# Escon.net
KiCad netlist of a schematic drawn in EAGLE
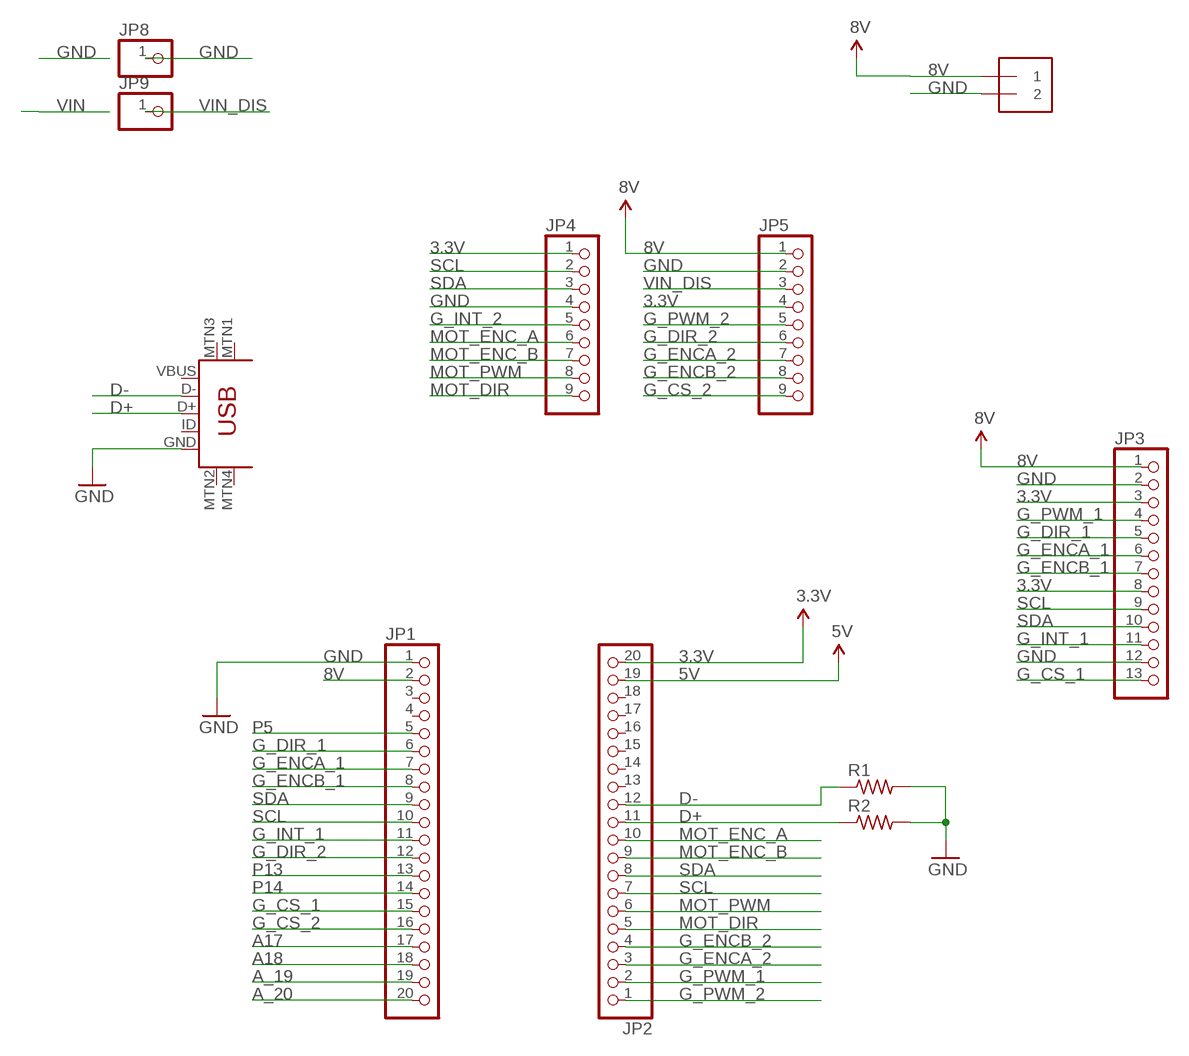
[diagram p0: schematic, sheet 1]

(export (version "E")
  (design (tool "Eeschema 10.0.6"))
  (components
    (comp (ref "J1")
      (value "1X2-3.5MM")
      (footprint "eagle-import:1X2-3.5MM")
      (libsource (lib "eagle-import") (part "1X2-3.5MM"))
    )
    (comp (ref "JP1")
      (value "PINHD-1X20")
      (footprint "eagle-import:1X20")
      (libsource (lib "eagle-import") (part "PINHD-1X20"))
    )
    (comp (ref "JP2")
      (value "PINHD-1X20")
      (footprint "eagle-import:1X20")
      (libsource (lib "eagle-import") (part "PINHD-1X20"))
    )
    (comp (ref "JP3")
      (value "PINHD-1X13")
      (footprint "eagle-import:1X13")
      (libsource (lib "eagle-import") (part "PINHD-1X13"))
    )
    (comp (ref "JP4")
      (value "PINHD-1X9")
      (footprint "eagle-import:1X09-BIG")
      (libsource (lib "eagle-import") (part "PINHD-1X9"))
    )
    (comp (ref "JP5")
      (value "PINHD-1X9")
      (footprint "eagle-import:1X09-BIG")
      (libsource (lib "eagle-import") (part "PINHD-1X9"))
    )
    (comp (ref "JP8")
      (value "PINHD-1X1")
      (footprint "eagle-import:1X01")
      (libsource (lib "eagle-import") (part "PINHD-1X1"))
    )
    (comp (ref "JP9")
      (value "PINHD-1X1")
      (footprint "eagle-import:1X01")
      (libsource (lib "eagle-import") (part "PINHD-1X1"))
    )
    (comp (ref "R1")
      (value "RES-US1206")
      (footprint "eagle-import:R1206")
      (libsource (lib "eagle-import") (part "RES-US1206"))
    )
    (comp (ref "R2")
      (value "RES-US1206")
      (footprint "eagle-import:R1206")
      (libsource (lib "eagle-import") (part "RES-US1206"))
    )
    (comp (ref "U$1")
      (value "USB-MINIB-5PIN")
      (footprint "eagle-import:USB-MINIB")
      (libsource (lib "eagle-import") (part "USB-MINIB-5PIN"))
    )
  )
  (nets
    (net (code "1") (name "/A17") (class "Default")
      (node (ref "JP1") (pin "17") (pinfunction "17_17") (pintype "passive"))
    )
    (net (code "2") (name "/A18") (class "Default")
      (node (ref "JP1") (pin "18") (pinfunction "18_18") (pintype "passive"))
    )
    (net (code "3") (name "/A_19") (class "Default")
      (node (ref "JP1") (pin "19") (pinfunction "19_19") (pintype "passive"))
    )
    (net (code "4") (name "/A_20") (class "Default")
      (node (ref "JP1") (pin "20") (pinfunction "20_20") (pintype "passive"))
    )
    (net (code "5") (name "/D+") (class "Default")
      (node (ref "JP2") (pin "11") (pinfunction "11_11") (pintype "passive"))
      (node (ref "R2") (pin "1") (pinfunction "1_1") (pintype "passive"))
      (node (ref "U$1") (pin "D+") (pinfunction "D+_D+") (pintype "bidirectional"))
    )
    (net (code "6") (name "/D-") (class "Default")
      (node (ref "JP2") (pin "12") (pinfunction "12_12") (pintype "passive"))
      (node (ref "R1") (pin "1") (pinfunction "1_1") (pintype "passive"))
      (node (ref "U$1") (pin "D-") (pinfunction "D-_D-") (pintype "bidirectional"))
    )
    (net (code "7") (name "/G_CS_1") (class "Default")
      (node (ref "JP1") (pin "15") (pinfunction "15_15") (pintype "passive"))
      (node (ref "JP3") (pin "13") (pinfunction "13_13") (pintype "passive"))
    )
    (net (code "8") (name "/G_CS_2") (class "Default")
      (node (ref "JP1") (pin "16") (pinfunction "16_16") (pintype "passive"))
      (node (ref "JP5") (pin "9") (pinfunction "9_9") (pintype "passive"))
    )
    (net (code "9") (name "/G_DIR_1") (class "Default")
      (node (ref "JP1") (pin "6") (pinfunction "6_6") (pintype "passive"))
      (node (ref "JP3") (pin "5") (pinfunction "5_5") (pintype "passive"))
    )
    (net (code "10") (name "/G_DIR_2") (class "Default")
      (node (ref "JP1") (pin "12") (pinfunction "12_12") (pintype "passive"))
      (node (ref "JP5") (pin "6") (pinfunction "6_6") (pintype "passive"))
    )
    (net (code "11") (name "/G_ENCA_1") (class "Default")
      (node (ref "JP1") (pin "7") (pinfunction "7_7") (pintype "passive"))
      (node (ref "JP3") (pin "6") (pinfunction "6_6") (pintype "passive"))
    )
    (net (code "12") (name "/G_ENCA_2") (class "Default")
      (node (ref "JP2") (pin "3") (pinfunction "3_3") (pintype "passive"))
      (node (ref "JP5") (pin "7") (pinfunction "7_7") (pintype "passive"))
    )
    (net (code "13") (name "/G_ENCB_1") (class "Default")
      (node (ref "JP1") (pin "8") (pinfunction "8_8") (pintype "passive"))
      (node (ref "JP3") (pin "7") (pinfunction "7_7") (pintype "passive"))
    )
    (net (code "14") (name "/G_ENCB_2") (class "Default")
      (node (ref "JP2") (pin "4") (pinfunction "4_4") (pintype "passive"))
      (node (ref "JP5") (pin "8") (pinfunction "8_8") (pintype "passive"))
    )
    (net (code "15") (name "/G_INT_1") (class "Default")
      (node (ref "JP1") (pin "11") (pinfunction "11_11") (pintype "passive"))
      (node (ref "JP3") (pin "11") (pinfunction "11_11") (pintype "passive"))
    )
    (net (code "16") (name "/G_INT_2") (class "Default")
      (node (ref "JP4") (pin "5") (pinfunction "5_5") (pintype "passive"))
    )
    (net (code "17") (name "/G_PWM_1") (class "Default")
      (node (ref "JP2") (pin "2") (pinfunction "2_2") (pintype "passive"))
      (node (ref "JP3") (pin "4") (pinfunction "4_4") (pintype "passive"))
    )
    (net (code "18") (name "/G_PWM_2") (class "Default")
      (node (ref "JP2") (pin "1") (pinfunction "1_1") (pintype "passive"))
      (node (ref "JP5") (pin "5") (pinfunction "5_5") (pintype "passive"))
    )
    (net (code "19") (name "/MOT_DIR") (class "Default")
      (node (ref "JP2") (pin "5") (pinfunction "5_5") (pintype "passive"))
      (node (ref "JP4") (pin "9") (pinfunction "9_9") (pintype "passive"))
    )
    (net (code "20") (name "/MOT_ENC_A") (class "Default")
      (node (ref "JP2") (pin "10") (pinfunction "10_10") (pintype "passive"))
      (node (ref "JP4") (pin "6") (pinfunction "6_6") (pintype "passive"))
    )
    (net (code "21") (name "/MOT_ENC_B") (class "Default")
      (node (ref "JP2") (pin "9") (pinfunction "9_9") (pintype "passive"))
      (node (ref "JP4") (pin "7") (pinfunction "7_7") (pintype "passive"))
    )
    (net (code "22") (name "/MOT_PWM") (class "Default")
      (node (ref "JP2") (pin "6") (pinfunction "6_6") (pintype "passive"))
      (node (ref "JP4") (pin "8") (pinfunction "8_8") (pintype "passive"))
    )
    (net (code "23") (name "/P5") (class "Default")
      (node (ref "JP1") (pin "5") (pinfunction "5_5") (pintype "passive"))
    )
    (net (code "24") (name "/P13") (class "Default")
      (node (ref "JP1") (pin "13") (pinfunction "13_13") (pintype "passive"))
    )
    (net (code "25") (name "/P14") (class "Default")
      (node (ref "JP1") (pin "14") (pinfunction "14_14") (pintype "passive"))
    )
    (net (code "26") (name "/SCL") (class "Default")
      (node (ref "JP1") (pin "10") (pinfunction "10_10") (pintype "passive"))
      (node (ref "JP2") (pin "7") (pinfunction "7_7") (pintype "passive"))
      (node (ref "JP3") (pin "9") (pinfunction "9_9") (pintype "passive"))
      (node (ref "JP4") (pin "2") (pinfunction "2_2") (pintype "passive"))
    )
    (net (code "27") (name "/SDA") (class "Default")
      (node (ref "JP1") (pin "9") (pinfunction "9_9") (pintype "passive"))
      (node (ref "JP2") (pin "8") (pinfunction "8_8") (pintype "passive"))
      (node (ref "JP3") (pin "10") (pinfunction "10_10") (pintype "passive"))
      (node (ref "JP4") (pin "3") (pinfunction "3_3") (pintype "passive"))
    )
    (net (code "29") (name "/VIN_DIS") (class "Default")
      (node (ref "JP5") (pin "3") (pinfunction "3_3") (pintype "passive"))
      (node (ref "JP9") (pin "1") (pinfunction "1_1") (pintype "passive"))
    )
    (net (code "30") (name "3.3V") (class "Default")
      (node (ref "JP2") (pin "20") (pinfunction "20_20") (pintype "passive"))
      (node (ref "JP3") (pin "3") (pinfunction "3_3") (pintype "passive"))
      (node (ref "JP3") (pin "8") (pinfunction "8_8") (pintype "passive"))
      (node (ref "JP4") (pin "1") (pinfunction "1_1") (pintype "passive"))
      (node (ref "JP5") (pin "4") (pinfunction "4_4") (pintype "passive"))
    )
    (net (code "31") (name "5V") (class "Default")
      (node (ref "JP2") (pin "19") (pinfunction "19_19") (pintype "passive"))
    )
    (net (code "32") (name "8V") (class "Default")
      (node (ref "J1") (pin "1") (pinfunction "1_1") (pintype "passive"))
      (node (ref "JP1") (pin "2") (pinfunction "2_2") (pintype "passive"))
      (node (ref "JP3") (pin "1") (pinfunction "1_1") (pintype "passive"))
      (node (ref "JP5") (pin "1") (pinfunction "1_1") (pintype "passive"))
    )
    (net (code "33") (name "GND") (class "Default")
      (node (ref "J1") (pin "2") (pinfunction "2_2") (pintype "passive"))
      (node (ref "JP1") (pin "1") (pinfunction "1_1") (pintype "passive"))
      (node (ref "JP3") (pin "12") (pinfunction "12_12") (pintype "passive"))
      (node (ref "JP3") (pin "2") (pinfunction "2_2") (pintype "passive"))
      (node (ref "JP4") (pin "4") (pinfunction "4_4") (pintype "passive"))
      (node (ref "JP5") (pin "2") (pinfunction "2_2") (pintype "passive"))
      (node (ref "JP8") (pin "1") (pinfunction "1_1") (pintype "passive"))
      (node (ref "R1") (pin "2") (pinfunction "2_2") (pintype "passive"))
      (node (ref "R2") (pin "2") (pinfunction "2_2") (pintype "passive"))
      (node (ref "U$1") (pin "GND") (pinfunction "GND_GND") (pintype "bidirectional"))
    )
    (net (code "34") (name "unconnected-(JP1-Pad3)") (class "Default")
      (node (ref "JP1") (pin "3") (pinfunction "3_3") (pintype "passive"))
    )
    (net (code "35") (name "unconnected-(JP1-Pad4)") (class "Default")
      (node (ref "JP1") (pin "4") (pinfunction "4_4") (pintype "passive"))
    )
    (net (code "36") (name "unconnected-(JP2-Pad13)") (class "Default")
      (node (ref "JP2") (pin "13") (pinfunction "13_13") (pintype "passive"))
    )
    (net (code "37") (name "unconnected-(JP2-Pad14)") (class "Default")
      (node (ref "JP2") (pin "14") (pinfunction "14_14") (pintype "passive"))
    )
    (net (code "38") (name "unconnected-(JP2-Pad15)") (class "Default")
      (node (ref "JP2") (pin "15") (pinfunction "15_15") (pintype "passive"))
    )
    (net (code "39") (name "unconnected-(JP2-Pad16)") (class "Default")
      (node (ref "JP2") (pin "16") (pinfunction "16_16") (pintype "passive"))
    )
    (net (code "40") (name "unconnected-(JP2-Pad17)") (class "Default")
      (node (ref "JP2") (pin "17") (pinfunction "17_17") (pintype "passive"))
    )
    (net (code "41") (name "unconnected-(JP2-Pad18)") (class "Default")
      (node (ref "JP2") (pin "18") (pinfunction "18_18") (pintype "passive"))
    )
    (net (code "42") (name "unconnected-(U$1-MTN1-PadMTN3)") (class "Default")
      (node (ref "U$1") (pin "MTN3") (pinfunction "MTN1_MTN3") (pintype "bidirectional"))
    )
    (net (code "43") (name "unconnected-(U$1-MTN2-PadMTN1)") (class "Default")
      (node (ref "U$1") (pin "MTN1") (pinfunction "MTN2_MTN1") (pintype "bidirectional"))
    )
    (net (code "44") (name "unconnected-(U$1-MTN3-PadMTN2)") (class "Default")
      (node (ref "U$1") (pin "MTN2") (pinfunction "MTN3_MTN2") (pintype "bidirectional"))
    )
    (net (code "45") (name "unconnected-(U$1-PadID)") (class "Default")
      (node (ref "U$1") (pin "ID") (pinfunction "ID_ID") (pintype "bidirectional"))
    )
    (net (code "46") (name "unconnected-(U$1-PadMTN4)") (class "Default")
      (node (ref "U$1") (pin "MTN4") (pinfunction "MTN4_MTN4") (pintype "bidirectional"))
    )
    (net (code "47") (name "unconnected-(U$1-PadVBUS)") (class "Default")
      (node (ref "U$1") (pin "VBUS") (pinfunction "VBUS_VBUS") (pintype "bidirectional"))
    )
  )
)
